# controller.net
KiCad netlist of a schematic drawn in EAGLE
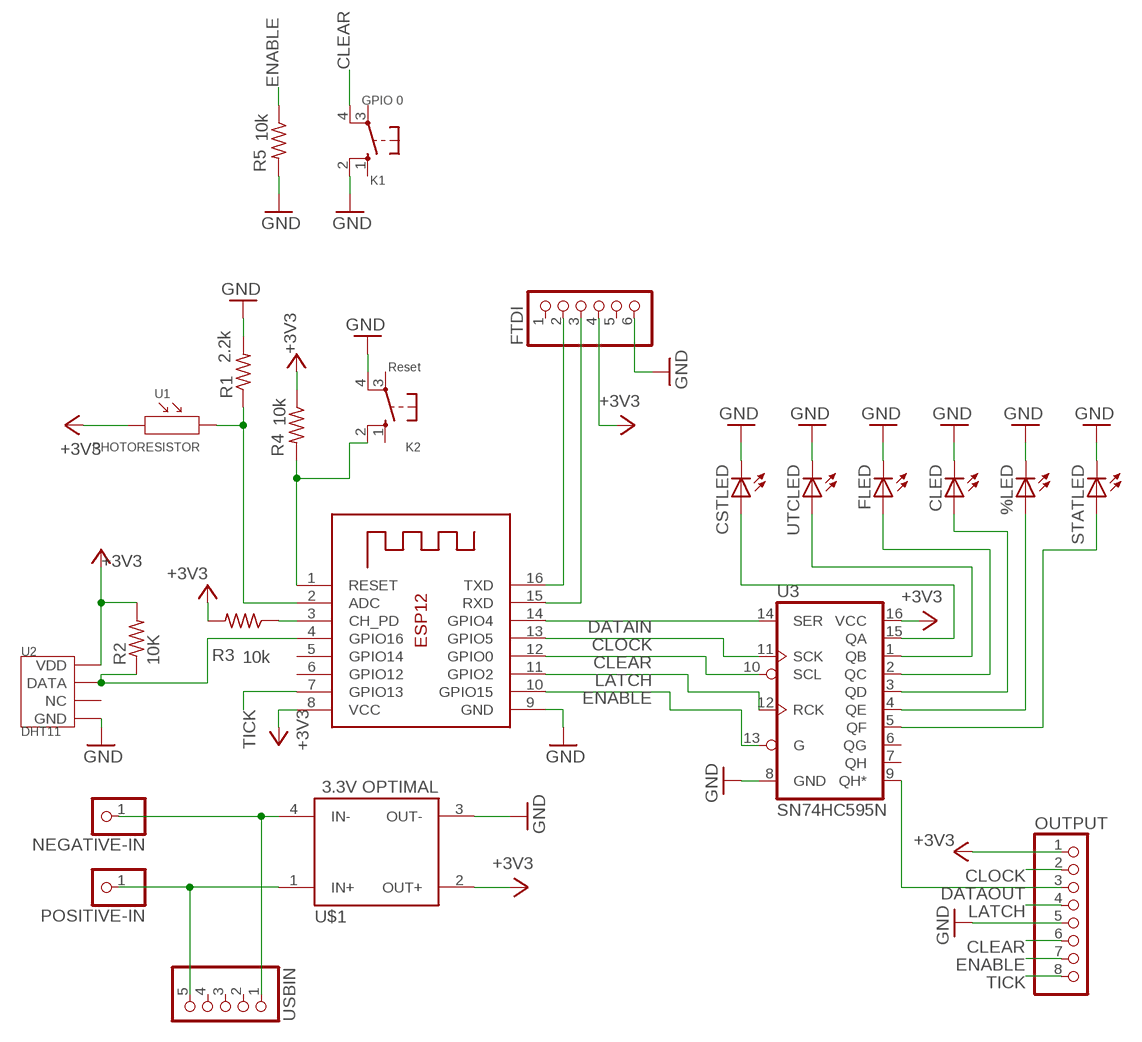
[diagram p0: schematic, sheet 1]

(export (version "E")
  (design (tool "Eeschema 10.0.6"))
  (components
    (comp (ref "%LED")
      (value "LED5MM")
      (footprint "eagle-import:LED5MM")
      (libsource (lib "eagle-import") (part "LED5MM"))
    )
    (comp (ref "CLED")
      (value "LED5MM")
      (footprint "eagle-import:LED5MM")
      (libsource (lib "eagle-import") (part "LED5MM"))
    )
    (comp (ref "CSTLED")
      (value "LED5MM")
      (footprint "eagle-import:LED5MM")
      (libsource (lib "eagle-import") (part "LED5MM"))
    )
    (comp (ref "FLED")
      (value "LED5MM")
      (footprint "eagle-import:LED5MM")
      (libsource (lib "eagle-import") (part "LED5MM"))
    )
    (comp (ref "FTDI")
      (value "PINHD-1X6/90")
      (footprint "eagle-import:1X06_90")
      (libsource (lib "eagle-import") (part "PINHD-1X6/90"))
    )
    (comp (ref "K1")
      (value "GPIO 0")
      (footprint "eagle-import:B3F-40XX")
      (fields (field (name "MF") "OMRON COMPONENTS USA") (field (name "MPN") "B3F-4000"))
      (libsource (lib "eagle-import") (part "40-XX"))
    )
    (comp (ref "K2")
      (value "Reset")
      (footprint "eagle-import:B3F-40XX")
      (fields (field (name "MF") "OMRON COMPONENTS USA") (field (name "MPN") "B3F-4000"))
      (libsource (lib "eagle-import") (part "40-XX"))
    )
    (comp (ref "NEGATIVE-IN")
      (value "PINHD-1X1")
      (footprint "eagle-import:1X01")
      (libsource (lib "eagle-import") (part "PINHD-1X1"))
    )
    (comp (ref "OUTPUT")
      (value "PINHD-1X8/90")
      (footprint "eagle-import:1X08_90")
      (libsource (lib "eagle-import") (part "PINHD-1X8/90"))
    )
    (comp (ref "POSITIVE-IN")
      (value "PINHD-1X1")
      (footprint "eagle-import:1X01")
      (libsource (lib "eagle-import") (part "PINHD-1X1"))
    )
    (comp (ref "R1")
      (value "2.2k")
      (footprint "eagle-import:0204_7")
      (libsource (lib "eagle-import") (part "R-US_0204/7"))
    )
    (comp (ref "R2")
      (value "10K")
      (footprint "eagle-import:0204_7")
      (libsource (lib "eagle-import") (part "R-US_0204/7"))
    )
    (comp (ref "R3")
      (value "10k")
      (footprint "eagle-import:0204_7")
      (libsource (lib "eagle-import") (part "R-US_0204/7"))
    )
    (comp (ref "R4")
      (value "10k")
      (footprint "eagle-import:0204_7")
      (libsource (lib "eagle-import") (part "R-US_0204/7"))
    )
    (comp (ref "R5")
      (value "10k")
      (footprint "eagle-import:0204_7")
      (libsource (lib "eagle-import") (part "R-US_0204/7"))
    )
    (comp (ref "STATLED")
      (value "LED5MM")
      (footprint "eagle-import:LED5MM")
      (libsource (lib "eagle-import") (part "LED5MM"))
    )
    (comp (ref "U$1")
      (value "3.3V OPTIMAL")
      (footprint "eagle-import:DIODFN1720X2240X160-4N")
      (libsource (lib "eagle-import") (part "COMPACTDC-DC"))
    )
    (comp (ref "U1")
      (value "PHOTORESISTOR")
      (footprint "eagle-import:SNR2-3.0")
      (fields (field (name "MPN") "PHOTORESISTOR-5528-10K"))
      (libsource (lib "eagle-import") (part "PHOTORESISTOR-5528-10K(2P-5.0X4.2MM)"))
    )
    (comp (ref "U2")
      (value "DHT11")
      (footprint "eagle-import:SNR4-2.54-15.5X12.0X5.5MM")
      (libsource (lib "eagle-import") (part "TEM-HUM-DHT11(4P-15.5X12.0MM)"))
    )
    (comp (ref "U3")
      (value "SN74HC595N")
      (footprint "eagle-import:DIP16")
      (libsource (lib "eagle-import") (part "74595NHC"))
    )
    (comp (ref "USBIN")
      (value "PINHD-1X5")
      (footprint "eagle-import:1X05")
      (libsource (lib "eagle-import") (part "PINHD-1X5"))
    )
    (comp (ref "UTCLED")
      (value "LED5MM")
      (footprint "eagle-import:LED5MM")
      (libsource (lib "eagle-import") (part "LED5MM"))
    )
    (comp (ref "X1")
      (value "ESP-12")
      (footprint "eagle-import:ESP-12")
      (libsource (lib "eagle-import") (part "ESP-12"))
    )
  )
  (nets
    (net (code "1") (name "+3V3") (class "Default")
      (node (ref "FTDI") (pin "4") (pinfunction "4_4") (pintype "passive"))
      (node (ref "OUTPUT") (pin "1") (pinfunction "1_1") (pintype "passive"))
      (node (ref "R2") (pin "2") (pinfunction "2_2") (pintype "passive"))
      (node (ref "R3") (pin "2") (pinfunction "2_2") (pintype "passive"))
      (node (ref "R4") (pin "1") (pinfunction "1_1") (pintype "passive"))
      (node (ref "U$1") (pin "2") (pinfunction "OUT+_2") (pintype "bidirectional"))
      (node (ref "U1") (pin "1") (pinfunction "P$1_1") (pintype "bidirectional"))
      (node (ref "U2") (pin "1") (pinfunction "VDD_1") (pintype "power_in"))
      (node (ref "U3") (pin "16") (pinfunction "VCC_16") (pintype "power_in"))
      (node (ref "X1") (pin "8") (pinfunction "VCC_8") (pintype "power_in"))
    )
    (net (code "2") (name "/CLEAR") (class "Default")
      (node (ref "K1") (pin "4") (pinfunction "P1_4") (pintype "passive"))
      (node (ref "OUTPUT") (pin "6") (pinfunction "6_6") (pintype "passive"))
      (node (ref "U3") (pin "10") (pinfunction "SCL_10") (pintype "input"))
      (node (ref "X1") (pin "12") (pinfunction "GPIO0_12") (pintype "bidirectional"))
    )
    (net (code "3") (name "/CLOCK") (class "Default")
      (node (ref "OUTPUT") (pin "2") (pinfunction "2_2") (pintype "passive"))
      (node (ref "U3") (pin "11") (pinfunction "SCK_11") (pintype "input"))
      (node (ref "X1") (pin "13") (pinfunction "GPIO5_13") (pintype "bidirectional"))
    )
    (net (code "4") (name "/DATAIN") (class "Default")
      (node (ref "U3") (pin "14") (pinfunction "SER_14") (pintype "input"))
      (node (ref "X1") (pin "14") (pinfunction "GPIO4_14") (pintype "bidirectional"))
    )
    (net (code "5") (name "/DATAOUT") (class "Default")
      (node (ref "OUTPUT") (pin "3") (pinfunction "3_3") (pintype "passive"))
      (node (ref "U3") (pin "9") (pinfunction "QH*_9") (pintype "tri_state"))
    )
    (net (code "6") (name "/ENABLE") (class "Default")
      (node (ref "OUTPUT") (pin "7") (pinfunction "7_7") (pintype "passive"))
      (node (ref "R5") (pin "1") (pinfunction "1_1") (pintype "passive"))
      (node (ref "U3") (pin "13") (pinfunction "G_13") (pintype "input"))
      (node (ref "X1") (pin "10") (pinfunction "GPIO15_10") (pintype "bidirectional"))
    )
    (net (code "7") (name "/LATCH") (class "Default")
      (node (ref "OUTPUT") (pin "4") (pinfunction "4_4") (pintype "passive"))
      (node (ref "U3") (pin "12") (pinfunction "RCK_12") (pintype "input"))
      (node (ref "X1") (pin "11") (pinfunction "GPIO2_11") (pintype "bidirectional"))
    )
    (net (code "8") (name "/TICK") (class "Default")
      (node (ref "OUTPUT") (pin "8") (pinfunction "8_8") (pintype "passive"))
      (node (ref "X1") (pin "7") (pinfunction "GPIO13_7") (pintype "bidirectional"))
    )
    (net (code "9") (name "GND") (class "Default")
      (node (ref "%LED") (pin "K") (pinfunction "C_K") (pintype "passive"))
      (node (ref "CLED") (pin "K") (pinfunction "C_K") (pintype "passive"))
      (node (ref "CSTLED") (pin "K") (pinfunction "C_K") (pintype "passive"))
      (node (ref "FLED") (pin "K") (pinfunction "C_K") (pintype "passive"))
      (node (ref "FTDI") (pin "6") (pinfunction "6_6") (pintype "passive"))
      (node (ref "K1") (pin "2") (pinfunction "S1_2") (pintype "passive"))
      (node (ref "K2") (pin "4") (pinfunction "P1_4") (pintype "passive"))
      (node (ref "OUTPUT") (pin "5") (pinfunction "5_5") (pintype "passive"))
      (node (ref "R1") (pin "2") (pinfunction "2_2") (pintype "passive"))
      (node (ref "R5") (pin "2") (pinfunction "2_2") (pintype "passive"))
      (node (ref "STATLED") (pin "K") (pinfunction "C_K") (pintype "passive"))
      (node (ref "U$1") (pin "3") (pinfunction "OUT-_3") (pintype "bidirectional"))
      (node (ref "U2") (pin "4") (pinfunction "GND_4") (pintype "power_in"))
      (node (ref "U3") (pin "8") (pinfunction "GND_8") (pintype "power_in"))
      (node (ref "UTCLED") (pin "K") (pinfunction "C_K") (pintype "passive"))
      (node (ref "X1") (pin "9") (pinfunction "GND_9") (pintype "power_in"))
    )
    (net (code "10") (name "Net-(K2-S1)") (class "Default")
      (node (ref "K2") (pin "2") (pinfunction "S1_2") (pintype "passive"))
      (node (ref "R4") (pin "2") (pinfunction "2_2") (pintype "passive"))
      (node (ref "X1") (pin "1") (pinfunction "RESET_1") (pintype "input"))
    )
    (net (code "11") (name "Net-(U$1-IN+)") (class "Default")
      (node (ref "POSITIVE-IN") (pin "1") (pinfunction "1_1") (pintype "passive"))
      (node (ref "U$1") (pin "1") (pinfunction "IN+_1") (pintype "bidirectional"))
      (node (ref "USBIN") (pin "5") (pinfunction "5_5") (pintype "passive"))
    )
    (net (code "12") (name "Net-(U$1-IN-)") (class "Default")
      (node (ref "NEGATIVE-IN") (pin "1") (pinfunction "1_1") (pintype "passive"))
      (node (ref "U$1") (pin "4") (pinfunction "IN-_4") (pintype "bidirectional"))
      (node (ref "USBIN") (pin "1") (pinfunction "1_1") (pintype "passive"))
    )
    (net (code "13") (name "Net-(U1-P$2)") (class "Default")
      (node (ref "R1") (pin "1") (pinfunction "1_1") (pintype "passive"))
      (node (ref "U1") (pin "2") (pinfunction "P$2_2") (pintype "bidirectional"))
      (node (ref "X1") (pin "2") (pinfunction "ADC_2") (pintype "passive"))
    )
    (net (code "14") (name "Net-(U2-DATA)") (class "Default")
      (node (ref "R2") (pin "1") (pinfunction "1_1") (pintype "passive"))
      (node (ref "U2") (pin "2") (pinfunction "DATA_2") (pintype "bidirectional"))
      (node (ref "X1") (pin "4") (pinfunction "GPIO16_4") (pintype "bidirectional"))
    )
    (net (code "15") (name "Net-(U3-QA)") (class "Default")
      (node (ref "CSTLED") (pin "A") (pinfunction "A_A") (pintype "passive"))
      (node (ref "U3") (pin "15") (pinfunction "QA_15") (pintype "tri_state"))
    )
    (net (code "16") (name "Net-(U3-QB)") (class "Default")
      (node (ref "U3") (pin "1") (pinfunction "QB_1") (pintype "tri_state"))
      (node (ref "UTCLED") (pin "A") (pinfunction "A_A") (pintype "passive"))
    )
    (net (code "17") (name "Net-(U3-QC)") (class "Default")
      (node (ref "FLED") (pin "A") (pinfunction "A_A") (pintype "passive"))
      (node (ref "U3") (pin "2") (pinfunction "QC_2") (pintype "tri_state"))
    )
    (net (code "18") (name "Net-(U3-QD)") (class "Default")
      (node (ref "CLED") (pin "A") (pinfunction "A_A") (pintype "passive"))
      (node (ref "U3") (pin "3") (pinfunction "QD_3") (pintype "tri_state"))
    )
    (net (code "19") (name "Net-(U3-QE)") (class "Default")
      (node (ref "%LED") (pin "A") (pinfunction "A_A") (pintype "passive"))
      (node (ref "U3") (pin "4") (pinfunction "QE_4") (pintype "tri_state"))
    )
    (net (code "20") (name "Net-(U3-QF)") (class "Default")
      (node (ref "STATLED") (pin "A") (pinfunction "A_A") (pintype "passive"))
      (node (ref "U3") (pin "5") (pinfunction "QF_5") (pintype "tri_state"))
    )
    (net (code "21") (name "Net-(X1-CH_PD)") (class "Default")
      (node (ref "R3") (pin "1") (pinfunction "1_1") (pintype "passive"))
      (node (ref "X1") (pin "3") (pinfunction "CH_PD_3") (pintype "input"))
    )
    (net (code "22") (name "Net-(X1-RXD)") (class "Default")
      (node (ref "FTDI") (pin "3") (pinfunction "3_3") (pintype "passive"))
      (node (ref "X1") (pin "15") (pinfunction "RXD_15") (pintype "input"))
    )
    (net (code "23") (name "Net-(X1-TXD)") (class "Default")
      (node (ref "FTDI") (pin "2") (pinfunction "2_2") (pintype "passive"))
      (node (ref "X1") (pin "16") (pinfunction "TXD_16") (pintype "output"))
    )
    (net (code "24") (name "unconnected-(FTDI-Pad1)") (class "Default")
      (node (ref "FTDI") (pin "1") (pinfunction "1_1") (pintype "passive"))
    )
    (net (code "25") (name "unconnected-(FTDI-Pad5)") (class "Default")
      (node (ref "FTDI") (pin "5") (pinfunction "5_5") (pintype "passive"))
    )
    (net (code "26") (name "unconnected-(K1-P-Pad3)") (class "Default")
      (node (ref "K1") (pin "3") (pinfunction "P_3") (pintype "passive"))
    )
    (net (code "27") (name "unconnected-(K1-S-Pad1)") (class "Default")
      (node (ref "K1") (pin "1") (pinfunction "S_1") (pintype "passive"))
    )
    (net (code "28") (name "unconnected-(K2-P-Pad3)") (class "Default")
      (node (ref "K2") (pin "3") (pinfunction "P_3") (pintype "passive"))
    )
    (net (code "29") (name "unconnected-(K2-S-Pad1)") (class "Default")
      (node (ref "K2") (pin "1") (pinfunction "S_1") (pintype "passive"))
    )
    (net (code "30") (name "unconnected-(U2-NC-Pad3)") (class "Default")
      (node (ref "U2") (pin "3") (pinfunction "NC_3") (pintype "no_connect"))
    )
    (net (code "31") (name "unconnected-(U3-QG-Pad6)") (class "Default")
      (node (ref "U3") (pin "6") (pinfunction "QG_6") (pintype "tri_state"))
    )
    (net (code "32") (name "unconnected-(U3-QH-Pad7)") (class "Default")
      (node (ref "U3") (pin "7") (pinfunction "QH_7") (pintype "tri_state"))
    )
    (net (code "33") (name "unconnected-(USBIN-Pad2)") (class "Default")
      (node (ref "USBIN") (pin "2") (pinfunction "2_2") (pintype "passive"))
    )
    (net (code "34") (name "unconnected-(USBIN-Pad3)") (class "Default")
      (node (ref "USBIN") (pin "3") (pinfunction "3_3") (pintype "passive"))
    )
    (net (code "35") (name "unconnected-(USBIN-Pad4)") (class "Default")
      (node (ref "USBIN") (pin "4") (pinfunction "4_4") (pintype "passive"))
    )
    (net (code "36") (name "unconnected-(X1-GPIO12-Pad6)") (class "Default")
      (node (ref "X1") (pin "6") (pinfunction "GPIO12_6") (pintype "bidirectional"))
    )
    (net (code "37") (name "unconnected-(X1-GPIO14-Pad5)") (class "Default")
      (node (ref "X1") (pin "5") (pinfunction "GPIO14_5") (pintype "bidirectional"))
    )
  )
)
